# rapidshark-battery-conn-mk-2_0.net
KiCad netlist of a schematic drawn in EAGLE
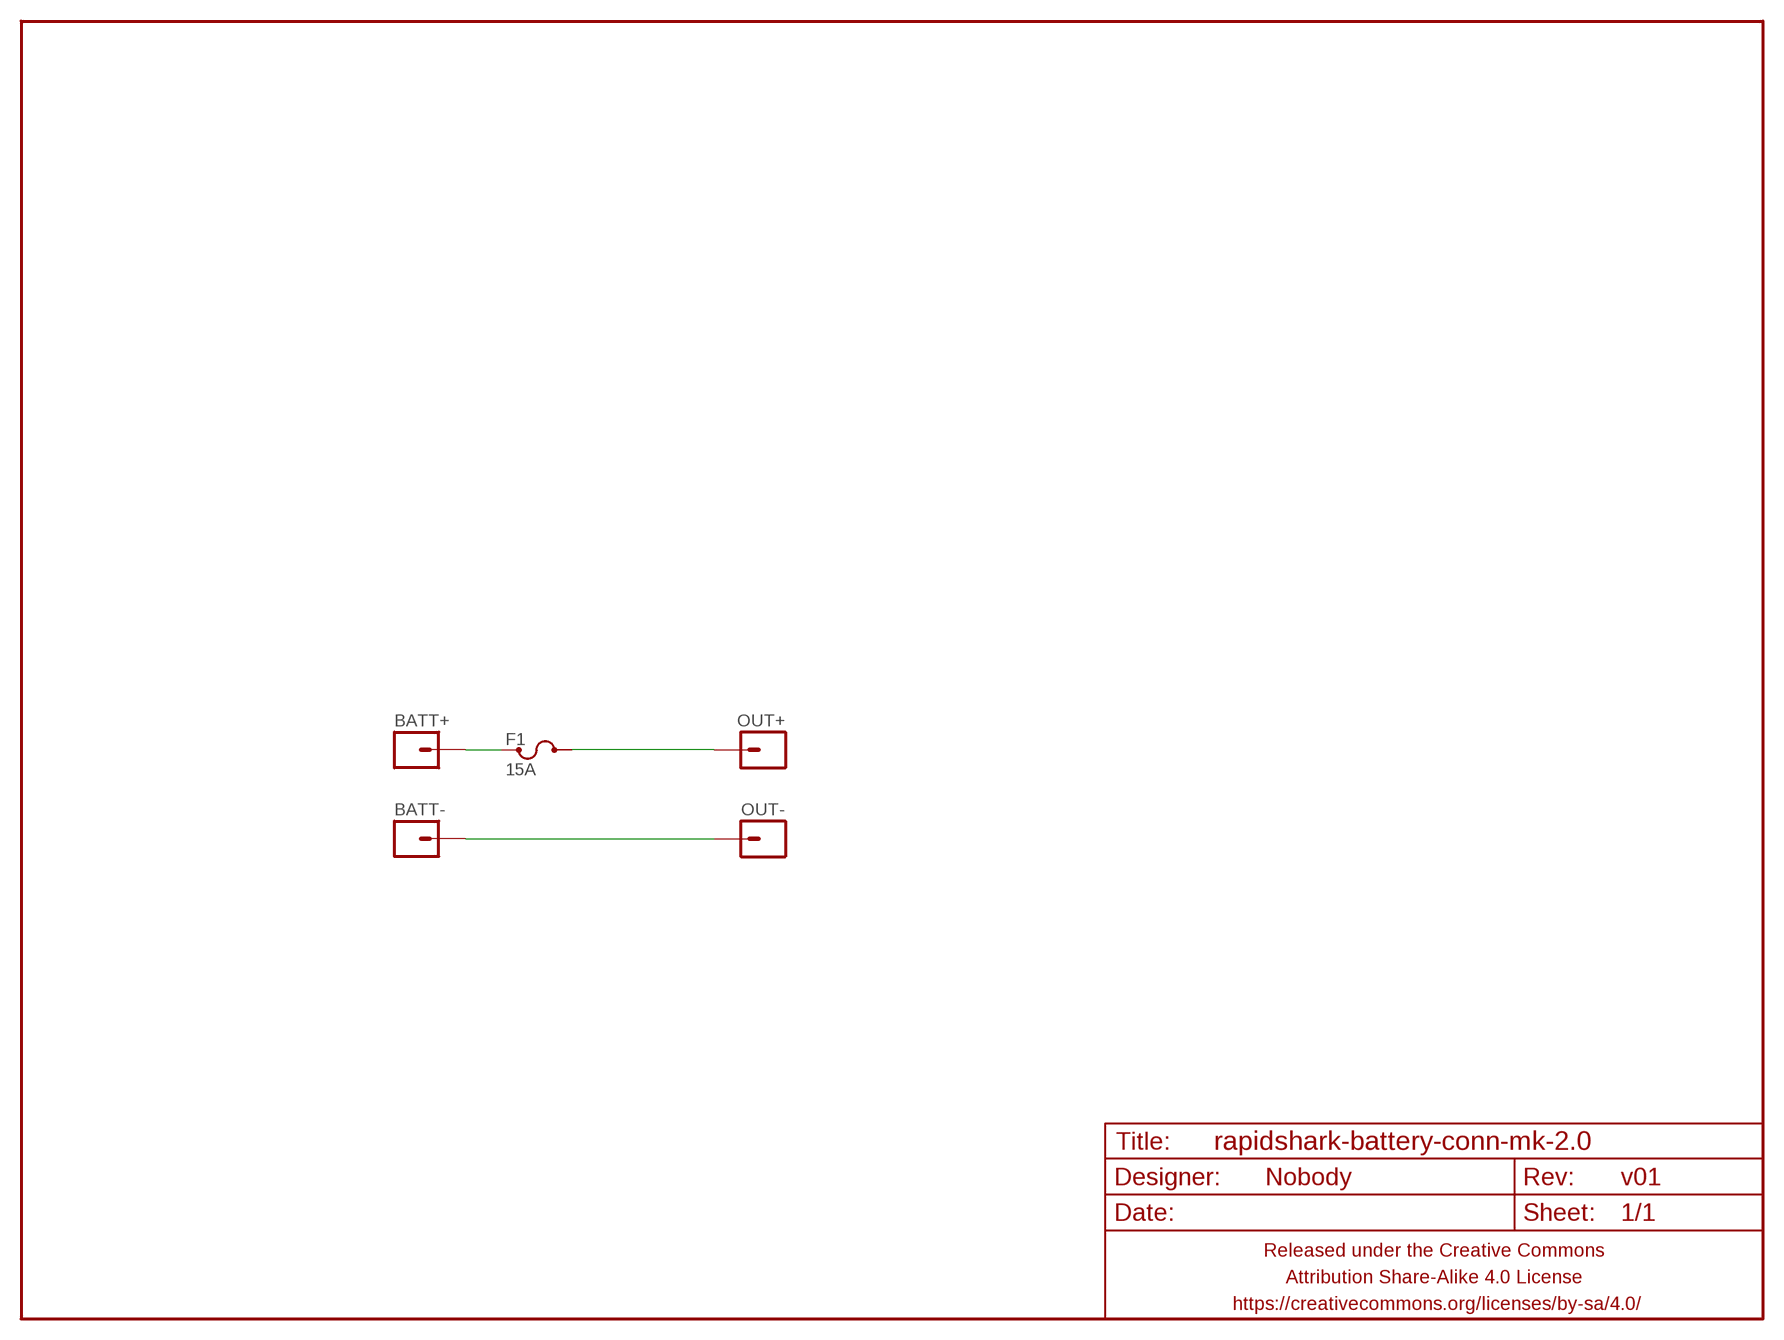
[diagram p0: schematic, sheet 1]

(export (version "E")
  (design (tool "Eeschema 10.0.6"))
  (components
    (comp (ref "BATT+")
      (value "M01PTH-2.3MM")
      (footprint "eagle-import:1X01-2.3MM")
      (libsource (lib "eagle-import") (part "M01PTH-2.3MM"))
    )
    (comp (ref "BATT-")
      (value "M01PTH-2.3MM")
      (footprint "eagle-import:1X01-2.3MM")
      (libsource (lib "eagle-import") (part "M01PTH-2.3MM"))
    )
    (comp (ref "F1")
      (value "15A")
      (footprint "eagle-import:KEYSTONE-MINI-AUTO-FUSE-HOLDER")
      (libsource (lib "eagle-import") (part "FUSEMINI-AUTO"))
    )
    (comp (ref "FRAME1")
      (value "FRAME-LETTERNO_PACKAGE")
      (footprint "eagle-import:DUMMY")
      (fields (field (name "DESIGNER") "Nobody"))
      (libsource (lib "eagle-import") (part "FRAME-LETTERNO_PACKAGE"))
    )
    (comp (ref "OUT+")
      (value "M0112AWG")
      (footprint "eagle-import:1X01-12AWG")
      (libsource (lib "eagle-import") (part "M0112AWG"))
    )
    (comp (ref "OUT-")
      (value "M0112AWG")
      (footprint "eagle-import:1X01-12AWG")
      (libsource (lib "eagle-import") (part "M0112AWG"))
    )
  )
  (nets
    (net (code "1") (name "Net-(BATT+-Pad1)") (class "Default")
      (node (ref "BATT+") (pin "1") (pinfunction "1_1") (pintype "passive"))
      (node (ref "F1") (pin "P1@1") (pinfunction "1_P1@1") (pintype "passive"))
      (node (ref "F1") (pin "P1@2") (pinfunction "1_P1@2") (pintype "passive"))
    )
    (net (code "2") (name "Net-(BATT--Pad1)") (class "Default")
      (node (ref "BATT-") (pin "1") (pinfunction "1_1") (pintype "passive"))
      (node (ref "OUT-") (pin "1") (pinfunction "1_1") (pintype "passive"))
    )
    (net (code "3") (name "Net-(F1-2-PadP2@1)") (class "Default")
      (node (ref "F1") (pin "P2@1") (pinfunction "2_P2@1") (pintype "passive"))
      (node (ref "F1") (pin "P2@2") (pinfunction "2_P2@2") (pintype "passive"))
      (node (ref "OUT+") (pin "1") (pinfunction "1_1") (pintype "passive"))
    )
  )
)
